# tick-box-1591A-mk-2_1.net
KiCad netlist of a schematic drawn in EAGLE
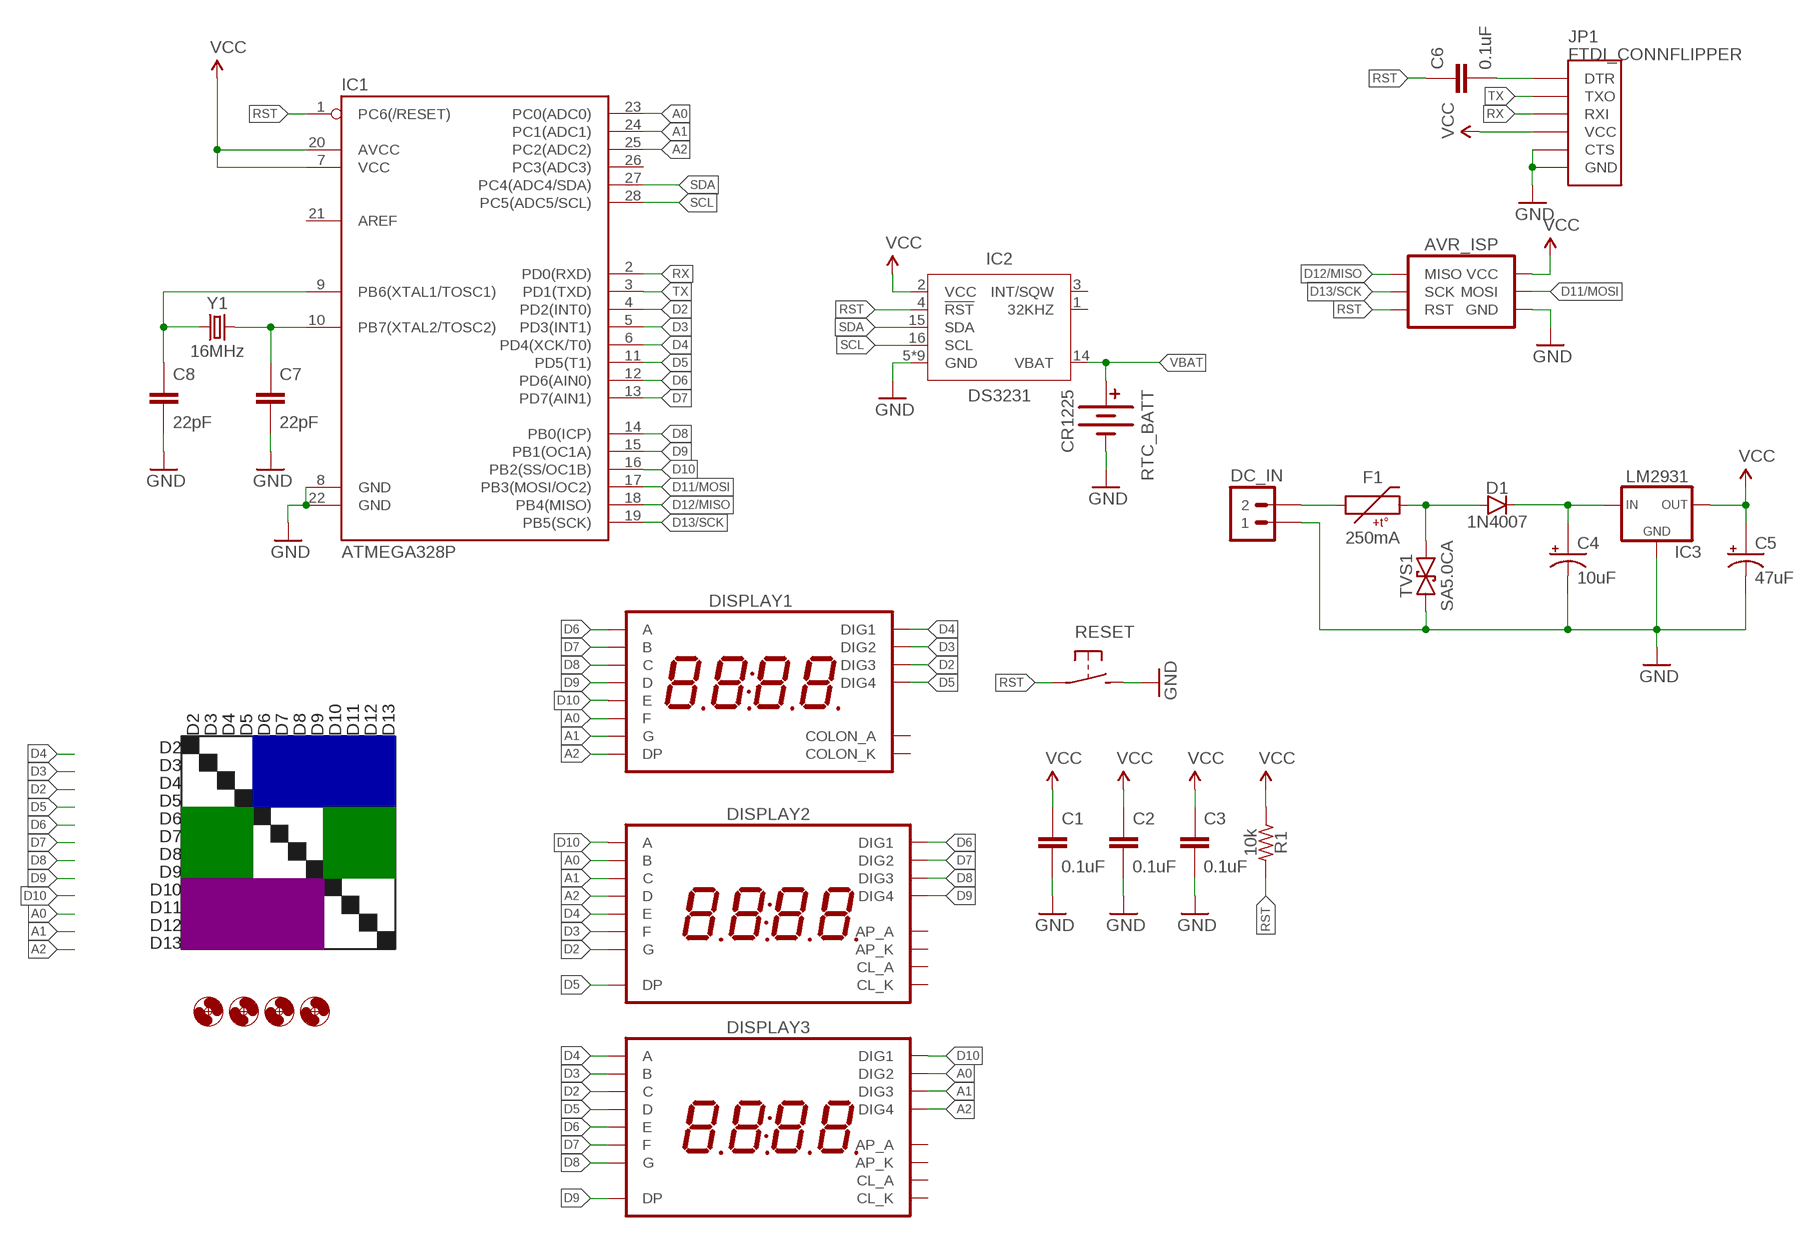
[diagram p0: schematic, sheet 1]

(export (version "E")
  (design (tool "Eeschema 10.0.6"))
  (components
    (comp (ref "AVR_ISP")
      (value "AVR_SPI_PRG_6PTH")
      (footprint "eagle-import:2X3")
      (libsource (lib "eagle-import") (part "AVR_SPI_PRG_6PTH"))
    )
    (comp (ref "C1")
      (value "0.1uF")
      (footprint "eagle-import:C025-024X044")
      (libsource (lib "eagle-import") (part "CAPACITOR-CERAMIC025-024X044"))
    )
    (comp (ref "C2")
      (value "0.1uF")
      (footprint "eagle-import:C025-024X044")
      (libsource (lib "eagle-import") (part "CAPACITOR-CERAMIC025-024X044"))
    )
    (comp (ref "C3")
      (value "0.1uF")
      (footprint "eagle-import:C025-024X044")
      (libsource (lib "eagle-import") (part "CAPACITOR-CERAMIC025-024X044"))
    )
    (comp (ref "C4")
      (value "10uF")
      (footprint "eagle-import:E2-4")
      (libsource (lib "eagle-import") (part "CAPACITOR-POLARIZEDE2-4"))
    )
    (comp (ref "C5")
      (value "47uF")
      (footprint "eagle-import:E2-4")
      (libsource (lib "eagle-import") (part "CAPACITOR-POLARIZEDE2-4"))
    )
    (comp (ref "C6")
      (value "0.1uF")
      (footprint "eagle-import:C025-024X044")
      (libsource (lib "eagle-import") (part "CAPACITOR-CERAMIC025-024X044"))
    )
    (comp (ref "C7")
      (value "22pF")
      (footprint "eagle-import:C025-024X044")
      (libsource (lib "eagle-import") (part "CAPACITOR-CERAMIC025-024X044"))
    )
    (comp (ref "C8")
      (value "22pF")
      (footprint "eagle-import:C025-024X044")
      (libsource (lib "eagle-import") (part "CAPACITOR-CERAMIC025-024X044"))
    )
    (comp (ref "D1")
      (value "1N4007")
      (footprint "eagle-import:DIODE-10.16MM")
      (libsource (lib "eagle-import") (part "DIODEPTH-10.68MM"))
    )
    (comp (ref "DC_IN")
      (value "M02PTH")
      (footprint "eagle-import:1X02")
      (libsource (lib "eagle-import") (part "M02PTH"))
    )
    (comp (ref "DISPLAY1")
      (value "7SEG_4DIGIT_COLON14.2MM-CC-NS")
      (footprint "eagle-import:7SEG_4DIG_NS")
      (libsource (lib "eagle-import") (part "7SEG_4DIGIT_COLON14.2MM-CC-NS"))
    )
    (comp (ref "DISPLAY2")
      (value "7SEG_4DIGIT_COLON_APOS")
      (footprint "eagle-import:7SEG_4DIG_10MM")
      (libsource (lib "eagle-import") (part "7SEG_4DIGIT_COLON_APOS"))
    )
    (comp (ref "DISPLAY3")
      (value "7SEG_4DIGIT_COLON_APOS")
      (footprint "eagle-import:7SEG_4DIG_10MM")
      (libsource (lib "eagle-import") (part "7SEG_4DIGIT_COLON_APOS"))
    )
    (comp (ref "F1")
      (value "250mA")
      (footprint "eagle-import:PTC-PTH-5.08MM")
      (libsource (lib "eagle-import") (part "PTCPTH-5.08MM"))
    )
    (comp (ref "H1")
      (value "HOLE#2")
      (footprint "eagle-import:HOLE-#2")
      (libsource (lib "eagle-import") (part "HOLE#2"))
    )
    (comp (ref "H2")
      (value "HOLE#2")
      (footprint "eagle-import:HOLE-#2")
      (libsource (lib "eagle-import") (part "HOLE#2"))
    )
    (comp (ref "H3")
      (value "HOLE#2")
      (footprint "eagle-import:HOLE-#2")
      (libsource (lib "eagle-import") (part "HOLE#2"))
    )
    (comp (ref "H4")
      (value "HOLE#2")
      (footprint "eagle-import:HOLE-#2")
      (libsource (lib "eagle-import") (part "HOLE#2"))
    )
    (comp (ref "IC1")
      (value "ATMEGA328P")
      (footprint "eagle-import:DIL28-3")
      (libsource (lib "eagle-import") (part "ATMEGA328P_PDIP"))
    )
    (comp (ref "IC2")
      (value "DS3231")
      (footprint "eagle-import:SO16W")
      (libsource (lib "eagle-import") (part "DS3231"))
    )
    (comp (ref "IC3")
      (value "LM2931")
      (footprint "eagle-import:TO-92-AMMO")
      (libsource (lib "eagle-import") (part "V_REG_78XXTO-92-INLINE"))
    )
    (comp (ref "JP1")
      (value "FTDI_CONNFLIPPER")
      (footprint "eagle-import:FTDI_CONN_FLIP")
      (libsource (lib "eagle-import") (part "FTDI_CONNFLIPPER"))
    )
    (comp (ref "R1")
      (value "10k")
      (footprint "eagle-import:RESISTOR-AXIAL-PTH-6.35MM")
      (libsource (lib "eagle-import") (part "RESISTORPTH-AXIAL-6.35MM"))
    )
    (comp (ref "RESET")
      (value "SPST-NO-TACT3MM-PTH-SMALL-PADS")
      (footprint "eagle-import:DTS-3-SMALL-PADS")
      (libsource (lib "eagle-import") (part "SPST-NO-TACT3MM-PTH-SMALL-PADS"))
    )
    (comp (ref "RTC_BATT")
      (value "CR1225")
      (footprint "eagle-import:BATTCON_12MM_PTH_TOPLOAD")
      (libsource (lib "eagle-import") (part "BATTERY12PTH_TOPLOAD"))
    )
    (comp (ref "TVS1")
      (value "SA5.0CA")
      (footprint "eagle-import:DO-41-TVS-BI-10.16MM")
      (libsource (lib "eagle-import") (part "TVSDO-41-10.16MM"))
    )
    (comp (ref "Y1")
      (value "16MHz")
      (footprint "eagle-import:HC49U-V")
      (libsource (lib "eagle-import") (part "CRYSTALHC49UV"))
    )
  )
  (nets
    (net (code "1") (name "A0") (class "Default")
      (node (ref "DISPLAY1") (pin "P$12") (pinfunction "F_P$12") (pintype "passive"))
      (node (ref "DISPLAY2") (pin "16") (pinfunction "B_16") (pintype "passive"))
      (node (ref "DISPLAY3") (pin "2") (pinfunction "DIG2_2") (pintype "passive"))
      (node (ref "IC1") (pin "23") (pinfunction "PC0(ADC0)_23") (pintype "bidirectional"))
    )
    (net (code "2") (name "A1") (class "Default")
      (node (ref "DISPLAY1") (pin "P$5") (pinfunction "G_P$5") (pintype "passive"))
      (node (ref "DISPLAY2") (pin "13") (pinfunction "C_13") (pintype "passive"))
      (node (ref "DISPLAY3") (pin "6") (pinfunction "DIG3_6") (pintype "passive"))
      (node (ref "IC1") (pin "24") (pinfunction "PC1(ADC1)_24") (pintype "bidirectional"))
    )
    (net (code "3") (name "A2") (class "Default")
      (node (ref "DISPLAY1") (pin "P$3") (pinfunction "DP_P$3") (pintype "passive"))
      (node (ref "DISPLAY2") (pin "3") (pinfunction "D_3") (pintype "passive"))
      (node (ref "DISPLAY3") (pin "8") (pinfunction "DIG4_8") (pintype "passive"))
      (node (ref "IC1") (pin "25") (pinfunction "PC2(ADC2)_25") (pintype "bidirectional"))
    )
    (net (code "4") (name "D2") (class "Default")
      (node (ref "DISPLAY1") (pin "P$10") (pinfunction "DIG3_P$10") (pintype "passive"))
      (node (ref "DISPLAY2") (pin "15") (pinfunction "G_15") (pintype "passive"))
      (node (ref "DISPLAY3") (pin "13") (pinfunction "C_13") (pintype "passive"))
      (node (ref "IC1") (pin "4") (pinfunction "PD2(INT0)_4") (pintype "bidirectional"))
    )
    (net (code "5") (name "D3") (class "Default")
      (node (ref "DISPLAY1") (pin "P$11") (pinfunction "DIG2_P$11") (pintype "passive"))
      (node (ref "DISPLAY2") (pin "11") (pinfunction "F_11") (pintype "passive"))
      (node (ref "DISPLAY3") (pin "16") (pinfunction "B_16") (pintype "passive"))
      (node (ref "IC1") (pin "5") (pinfunction "PD3(INT1)_5") (pintype "bidirectional"))
    )
    (net (code "6") (name "D4") (class "Default")
      (node (ref "DISPLAY1") (pin "P$14") (pinfunction "DIG1_P$14") (pintype "passive"))
      (node (ref "DISPLAY2") (pin "5") (pinfunction "E_5") (pintype "passive"))
      (node (ref "DISPLAY3") (pin "14") (pinfunction "A_14") (pintype "passive"))
      (node (ref "IC1") (pin "6") (pinfunction "PD4(XCK/T0)_6") (pintype "bidirectional"))
    )
    (net (code "7") (name "D5") (class "Default")
      (node (ref "DISPLAY1") (pin "P$6") (pinfunction "DIG4_P$6") (pintype "passive"))
      (node (ref "DISPLAY2") (pin "7") (pinfunction "DP_7") (pintype "passive"))
      (node (ref "DISPLAY3") (pin "3") (pinfunction "D_3") (pintype "passive"))
      (node (ref "IC1") (pin "11") (pinfunction "PD5(T1)_11") (pintype "bidirectional"))
    )
    (net (code "8") (name "D6") (class "Default")
      (node (ref "DISPLAY1") (pin "P$13") (pinfunction "A_P$13") (pintype "passive"))
      (node (ref "DISPLAY2") (pin "1") (pinfunction "DIG1_1") (pintype "passive"))
      (node (ref "DISPLAY3") (pin "5") (pinfunction "E_5") (pintype "passive"))
      (node (ref "IC1") (pin "12") (pinfunction "PD6(AIN0)_12") (pintype "bidirectional"))
    )
    (net (code "9") (name "D7") (class "Default")
      (node (ref "DISPLAY1") (pin "P$9") (pinfunction "B_P$9") (pintype "passive"))
      (node (ref "DISPLAY2") (pin "2") (pinfunction "DIG2_2") (pintype "passive"))
      (node (ref "DISPLAY3") (pin "11") (pinfunction "F_11") (pintype "passive"))
      (node (ref "IC1") (pin "13") (pinfunction "PD7(AIN1)_13") (pintype "bidirectional"))
    )
    (net (code "10") (name "D8") (class "Default")
      (node (ref "DISPLAY1") (pin "P$4") (pinfunction "C_P$4") (pintype "passive"))
      (node (ref "DISPLAY2") (pin "6") (pinfunction "DIG3_6") (pintype "passive"))
      (node (ref "DISPLAY3") (pin "15") (pinfunction "G_15") (pintype "passive"))
      (node (ref "IC1") (pin "14") (pinfunction "PB0(ICP)_14") (pintype "bidirectional"))
    )
    (net (code "11") (name "D9") (class "Default")
      (node (ref "DISPLAY1") (pin "P$2") (pinfunction "D_P$2") (pintype "passive"))
      (node (ref "DISPLAY2") (pin "8") (pinfunction "DIG4_8") (pintype "passive"))
      (node (ref "DISPLAY3") (pin "7") (pinfunction "DP_7") (pintype "passive"))
      (node (ref "IC1") (pin "15") (pinfunction "PB1(OC1A)_15") (pintype "bidirectional"))
    )
    (net (code "12") (name "D10") (class "Default")
      (node (ref "DISPLAY1") (pin "P$1") (pinfunction "E_P$1") (pintype "passive"))
      (node (ref "DISPLAY2") (pin "14") (pinfunction "A_14") (pintype "passive"))
      (node (ref "DISPLAY3") (pin "1") (pinfunction "DIG1_1") (pintype "passive"))
      (node (ref "IC1") (pin "16") (pinfunction "PB2(SS/OC1B)_16") (pintype "bidirectional"))
    )
    (net (code "13") (name "D11{slash}MOSI") (class "Default")
      (node (ref "AVR_ISP") (pin "4") (pinfunction "MOSI_4") (pintype "passive"))
      (node (ref "IC1") (pin "17") (pinfunction "PB3(MOSI/OC2)_17") (pintype "bidirectional"))
    )
    (net (code "14") (name "D12{slash}MISO") (class "Default")
      (node (ref "AVR_ISP") (pin "1") (pinfunction "MISO_1") (pintype "passive"))
      (node (ref "IC1") (pin "18") (pinfunction "PB4(MISO)_18") (pintype "bidirectional"))
    )
    (net (code "15") (name "D13{slash}SCK") (class "Default")
      (node (ref "AVR_ISP") (pin "3") (pinfunction "SCK_3") (pintype "passive"))
      (node (ref "IC1") (pin "19") (pinfunction "PB5(SCK)_19") (pintype "bidirectional"))
    )
    (net (code "16") (name "GND") (class "Default")
      (node (ref "AVR_ISP") (pin "6") (pinfunction "GND_6") (pintype "passive"))
      (node (ref "C1") (pin "2") (pinfunction "2_2") (pintype "passive"))
      (node (ref "C2") (pin "2") (pinfunction "2_2") (pintype "passive"))
      (node (ref "C3") (pin "2") (pinfunction "2_2") (pintype "passive"))
      (node (ref "C4") (pin "-") (pinfunction "-_-") (pintype "passive"))
      (node (ref "C5") (pin "-") (pinfunction "-_-") (pintype "passive"))
      (node (ref "C7") (pin "2") (pinfunction "2_2") (pintype "passive"))
      (node (ref "C8") (pin "2") (pinfunction "2_2") (pintype "passive"))
      (node (ref "DC_IN") (pin "1") (pinfunction "1_1") (pintype "passive"))
      (node (ref "IC1") (pin "22") (pinfunction "GND_22") (pintype "bidirectional"))
      (node (ref "IC1") (pin "8") (pinfunction "GND_8") (pintype "bidirectional"))
      (node (ref "IC2") (pin "10") (pinfunction "GND_10") (pintype "bidirectional"))
      (node (ref "IC2") (pin "11") (pinfunction "GND_11") (pintype "bidirectional"))
      (node (ref "IC2") (pin "12") (pinfunction "GND_12") (pintype "bidirectional"))
      (node (ref "IC2") (pin "13") (pinfunction "GND_13") (pintype "bidirectional"))
      (node (ref "IC2") (pin "5") (pinfunction "GND_5") (pintype "bidirectional"))
      (node (ref "IC2") (pin "6") (pinfunction "GND_6") (pintype "bidirectional"))
      (node (ref "IC2") (pin "7") (pinfunction "GND_7") (pintype "bidirectional"))
      (node (ref "IC2") (pin "8") (pinfunction "GND_8") (pintype "bidirectional"))
      (node (ref "IC2") (pin "9") (pinfunction "GND_9") (pintype "bidirectional"))
      (node (ref "IC3") (pin "2") (pinfunction "GND_2") (pintype "bidirectional"))
      (node (ref "JP1") (pin "CTS") (pinfunction "CTS_CTS") (pintype "bidirectional"))
      (node (ref "JP1") (pin "GND") (pinfunction "GND_GND") (pintype "bidirectional"))
      (node (ref "RESET") (pin "2") (pinfunction "2_2") (pintype "passive"))
      (node (ref "RTC_BATT") (pin "-") (pinfunction "-_-") (pintype "power_in"))
      (node (ref "TVS1") (pin "P$1") (pinfunction "1_P$1") (pintype "passive"))
    )
    (net (code "17") (name "Net-(C6-Pad2)") (class "Default")
      (node (ref "C6") (pin "2") (pinfunction "2_2") (pintype "passive"))
      (node (ref "JP1") (pin "DTR") (pinfunction "DTR_DTR") (pintype "bidirectional"))
    )
    (net (code "18") (name "Net-(F1-1)") (class "Default")
      (node (ref "DC_IN") (pin "2") (pinfunction "2_2") (pintype "passive"))
      (node (ref "F1") (pin "P$1") (pinfunction "1_P$1") (pintype "passive"))
    )
    (net (code "19") (name "Net-(F1-2)") (class "Default")
      (node (ref "D1") (pin "A") (pinfunction "A_A") (pintype "passive"))
      (node (ref "F1") (pin "P$2") (pinfunction "2_P$2") (pintype "passive"))
      (node (ref "TVS1") (pin "P$2") (pinfunction "2_P$2") (pintype "passive"))
    )
    (net (code "20") (name "Net-(IC1-PB6(XTAL1{slash}TOSC1))") (class "Default")
      (node (ref "C8") (pin "1") (pinfunction "1_1") (pintype "passive"))
      (node (ref "IC1") (pin "9") (pinfunction "PB6(XTAL1/TOSC1)_9") (pintype "bidirectional"))
      (node (ref "Y1") (pin "2") (pinfunction "2_2") (pintype "passive"))
    )
    (net (code "21") (name "Net-(IC1-PB7(XTAL2{slash}TOSC2))") (class "Default")
      (node (ref "C7") (pin "1") (pinfunction "1_1") (pintype "passive"))
      (node (ref "IC1") (pin "10") (pinfunction "PB7(XTAL2/TOSC2)_10") (pintype "bidirectional"))
      (node (ref "Y1") (pin "1") (pinfunction "1_1") (pintype "passive"))
    )
    (net (code "22") (name "Net-(IC3-IN)") (class "Default")
      (node (ref "C4") (pin "+") (pinfunction "+_+") (pintype "passive"))
      (node (ref "D1") (pin "C") (pinfunction "C_C") (pintype "passive"))
      (node (ref "IC3") (pin "1") (pinfunction "IN_1") (pintype "bidirectional"))
    )
    (net (code "23") (name "RST") (class "Default")
      (node (ref "AVR_ISP") (pin "5") (pinfunction "RST_5") (pintype "passive"))
      (node (ref "C6") (pin "1") (pinfunction "1_1") (pintype "passive"))
      (node (ref "IC1") (pin "1") (pinfunction "PC6(/RESET)_1") (pintype "bidirectional"))
      (node (ref "IC2") (pin "4") (pinfunction "~{RST}_4") (pintype "bidirectional"))
      (node (ref "R1") (pin "P$2") (pinfunction "2_P$2") (pintype "passive"))
      (node (ref "RESET") (pin "1") (pinfunction "1_1") (pintype "passive"))
    )
    (net (code "24") (name "RX") (class "Default")
      (node (ref "IC1") (pin "2") (pinfunction "PD0(RXD)_2") (pintype "bidirectional"))
      (node (ref "JP1") (pin "RXI") (pinfunction "RXI_RXI") (pintype "bidirectional"))
    )
    (net (code "25") (name "SCL") (class "Default")
      (node (ref "IC1") (pin "28") (pinfunction "PC5(ADC5/SCL)_28") (pintype "bidirectional"))
      (node (ref "IC2") (pin "16") (pinfunction "SCL_16") (pintype "bidirectional"))
    )
    (net (code "26") (name "SDA") (class "Default")
      (node (ref "IC1") (pin "27") (pinfunction "PC4(ADC4/SDA)_27") (pintype "bidirectional"))
      (node (ref "IC2") (pin "15") (pinfunction "SDA_15") (pintype "bidirectional"))
    )
    (net (code "27") (name "TX") (class "Default")
      (node (ref "IC1") (pin "3") (pinfunction "PD1(TXD)_3") (pintype "bidirectional"))
      (node (ref "JP1") (pin "TXO") (pinfunction "TXO_TXO") (pintype "bidirectional"))
    )
    (net (code "28") (name "VBAT") (class "Default")
      (node (ref "IC2") (pin "14") (pinfunction "VBAT_14") (pintype "bidirectional"))
      (node (ref "RTC_BATT") (pin "+") (pinfunction "+_+") (pintype "power_in"))
    )
    (net (code "29") (name "VCC") (class "Default")
      (node (ref "AVR_ISP") (pin "2") (pinfunction "VCC_2") (pintype "passive"))
      (node (ref "C1") (pin "1") (pinfunction "1_1") (pintype "passive"))
      (node (ref "C2") (pin "1") (pinfunction "1_1") (pintype "passive"))
      (node (ref "C3") (pin "1") (pinfunction "1_1") (pintype "passive"))
      (node (ref "C5") (pin "+") (pinfunction "+_+") (pintype "passive"))
      (node (ref "IC1") (pin "20") (pinfunction "AVCC_20") (pintype "bidirectional"))
      (node (ref "IC1") (pin "7") (pinfunction "VCC_7") (pintype "bidirectional"))
      (node (ref "IC2") (pin "2") (pinfunction "VCC_2") (pintype "bidirectional"))
      (node (ref "IC3") (pin "3") (pinfunction "OUT_3") (pintype "bidirectional"))
      (node (ref "JP1") (pin "VCC") (pinfunction "VCC_VCC") (pintype "bidirectional"))
      (node (ref "R1") (pin "P$1") (pinfunction "1_P$1") (pintype "passive"))
    )
    (net (code "30") (name "unconnected-(DISPLAY1-COLON_A-PadP$8)") (class "Default")
      (node (ref "DISPLAY1") (pin "P$8") (pinfunction "COLON_A_P$8") (pintype "passive"))
    )
    (net (code "31") (name "unconnected-(DISPLAY1-COLON_K-PadP$7)") (class "Default")
      (node (ref "DISPLAY1") (pin "P$7") (pinfunction "COLON_K_P$7") (pintype "passive"))
    )
    (net (code "32") (name "unconnected-(DISPLAY2-AP_A-Pad10)") (class "Default")
      (node (ref "DISPLAY2") (pin "10") (pinfunction "AP_A_10") (pintype "bidirectional"))
    )
    (net (code "33") (name "unconnected-(DISPLAY2-AP_K-Pad9)") (class "Default")
      (node (ref "DISPLAY2") (pin "9") (pinfunction "AP_K_9") (pintype "bidirectional"))
    )
    (net (code "34") (name "unconnected-(DISPLAY2-CL_A-Pad4)") (class "Default")
      (node (ref "DISPLAY2") (pin "4") (pinfunction "CL_A_4") (pintype "passive"))
    )
    (net (code "35") (name "unconnected-(DISPLAY2-CL_K-Pad12)") (class "Default")
      (node (ref "DISPLAY2") (pin "12") (pinfunction "CL_K_12") (pintype "passive"))
    )
    (net (code "36") (name "unconnected-(DISPLAY3-AP_A-Pad10)") (class "Default")
      (node (ref "DISPLAY3") (pin "10") (pinfunction "AP_A_10") (pintype "bidirectional"))
    )
    (net (code "37") (name "unconnected-(DISPLAY3-AP_K-Pad9)") (class "Default")
      (node (ref "DISPLAY3") (pin "9") (pinfunction "AP_K_9") (pintype "bidirectional"))
    )
    (net (code "38") (name "unconnected-(DISPLAY3-CL_A-Pad4)") (class "Default")
      (node (ref "DISPLAY3") (pin "4") (pinfunction "CL_A_4") (pintype "passive"))
    )
    (net (code "39") (name "unconnected-(DISPLAY3-CL_K-Pad12)") (class "Default")
      (node (ref "DISPLAY3") (pin "12") (pinfunction "CL_K_12") (pintype "passive"))
    )
    (net (code "40") (name "unconnected-(IC1-AREF-Pad21)") (class "Default")
      (node (ref "IC1") (pin "21") (pinfunction "AREF_21") (pintype "bidirectional"))
    )
    (net (code "41") (name "unconnected-(IC1-PC3(ADC3)-Pad26)") (class "Default")
      (node (ref "IC1") (pin "26") (pinfunction "PC3(ADC3)_26") (pintype "bidirectional"))
    )
    (net (code "42") (name "unconnected-(IC2-32KHZ-Pad1)") (class "Default")
      (node (ref "IC2") (pin "1") (pinfunction "32KHZ_1") (pintype "bidirectional"))
    )
    (net (code "43") (name "unconnected-(IC2-INT{slash}SQW-Pad3)") (class "Default")
      (node (ref "IC2") (pin "3") (pinfunction "INT/SQW_3") (pintype "bidirectional"))
    )
  )
)
